# 08_BATT.net
KiCad netlist of a schematic drawn in Altium Designer
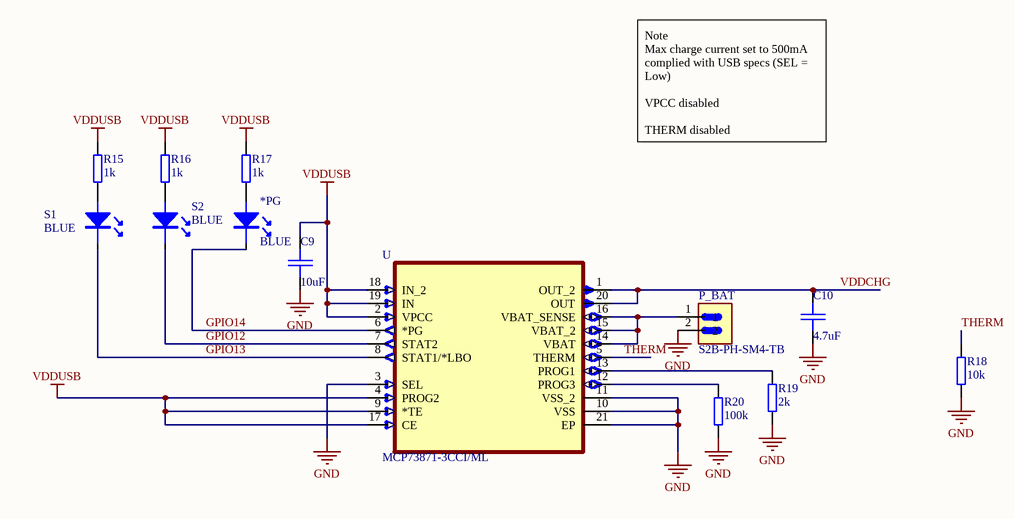
[diagram p0: 08_BATT.SchDoc]

(export (version "E")
  (design (tool "Eeschema 10.0.6"))
  (components
    (comp (ref "*PG")
      (value "BLUE")
      (footprint "SMT_LED_0603")
      (description "SMT LED")
      (libsource (lib "cupmat") (part "SMT_LED_0603"))
    )
    (comp (ref "C9")
      (value "10uF")
      (footprint "SMT_C_0402")
      (description "Surface mount capacitor 0402")
      (libsource (lib "cupmat") (part "SMT_C_0402"))
    )
    (comp (ref "C10")
      (value "4.7uF")
      (footprint "SMT_C_0402")
      (description "Surface mount capacitor 0402")
      (libsource (lib "cupmat") (part "SMT_C_0402"))
    )
    (comp (ref "P_BAT")
      (value "S2B-PH-SM4-TB")
      (footprint "JST_S2B-PH-SM4-TB")
      (description "Connector Header Surface Mount, Right Angle 2 position 0.079 _2.00mm_")
      (fields (field (name "MF") "JST Sales"))
      (libsource (lib "cupmat") (part "S2B-PH-SM4-TB"))
    )
    (comp (ref "R15")
      (value "1k")
      (footprint "SMT_R_0402")
      (description "Surface mount resistor 0402")
      (libsource (lib "cupmat") (part "SMT_R_0402"))
    )
    (comp (ref "R16")
      (value "1k")
      (footprint "SMT_R_0402")
      (description "Surface mount resistor 0402")
      (libsource (lib "cupmat") (part "SMT_R_0402"))
    )
    (comp (ref "R17")
      (value "1k")
      (footprint "SMT_R_0402")
      (description "Surface mount resistor 0402")
      (libsource (lib "cupmat") (part "SMT_R_0402"))
    )
    (comp (ref "R18")
      (value "10k")
      (footprint "SMT_R_0402")
      (description "Surface mount resistor 0402")
      (libsource (lib "cupmat") (part "SMT_R_0402"))
    )
    (comp (ref "R19")
      (value "2k")
      (footprint "SMT_R_0402")
      (description "Surface mount resistor 0402")
      (libsource (lib "cupmat") (part "SMT_R_0402"))
    )
    (comp (ref "R20")
      (value "100k")
      (footprint "SMT_R_0402")
      (description "Surface mount resistor 0402")
      (libsource (lib "cupmat") (part "SMT_R_0402"))
    )
    (comp (ref "S1")
      (value "BLUE")
      (footprint "SMT_LED_0603")
      (description "SMT LED")
      (libsource (lib "cupmat") (part "SMT_LED_0603"))
    )
    (comp (ref "S2")
      (value "BLUE")
      (footprint "SMT_LED_0603")
      (description "SMT LED")
      (libsource (lib "cupmat") (part "SMT_LED_0603"))
    )
    (comp (ref "U")
      (value "MCP73871-3CCI/ML")
      (footprint "MCP73871-3CCI/ML")
      (description "Charger IC Lithium Ion/Polymer 20-QFN _4x4_")
      (fields (field (name "MF") "Microchip"))
      (libsource (lib "cupmat") (part "MCP73871-3CCI/ML"))
    )
  )
  (nets
    (net (code "1") (name "/GPIO12") (class "Default")
      (node (ref "S2") (pin "2") (pinfunction "K_2") (pintype "passive"))
      (node (ref "U") (pin "7") (pinfunction "STAT2_7") (pintype "output"))
    )
    (net (code "2") (name "/GPIO13") (class "Default")
      (node (ref "S1") (pin "2") (pinfunction "K_2") (pintype "passive"))
      (node (ref "U") (pin "8") (pinfunction "STAT1/*LBO_8") (pintype "output"))
    )
    (net (code "3") (name "/GPIO14") (class "Default")
      (node (ref "*PG") (pin "2") (pinfunction "K_2") (pintype "passive"))
      (node (ref "U") (pin "6") (pinfunction "*PG_6") (pintype "output"))
    )
    (net (code "4") (name "/THERM") (class "Default")
      (node (ref "R18") (pin "2") (pinfunction "2_2") (pintype "passive"))
      (node (ref "U") (pin "5") (pinfunction "THERM_5") (pintype "bidirectional"))
    )
    (net (code "5") (name "/VDDCHG") (class "Default")
      (node (ref "C10") (pin "1") (pinfunction "1_1") (pintype "passive"))
      (node (ref "U") (pin "1") (pinfunction "OUT_2_1") (pintype "power_in"))
      (node (ref "U") (pin "20") (pinfunction "OUT_20") (pintype "power_in"))
    )
    (net (code "6") (name "GND") (class "Default")
      (node (ref "C10") (pin "2") (pinfunction "2_2") (pintype "passive"))
      (node (ref "C9") (pin "2") (pinfunction "2_2") (pintype "passive"))
      (node (ref "P_BAT") (pin "2") (pinfunction "2_2") (pintype "passive"))
      (node (ref "R18") (pin "1") (pinfunction "1_1") (pintype "passive"))
      (node (ref "R19") (pin "1") (pinfunction "1_1") (pintype "passive"))
      (node (ref "R20") (pin "1") (pinfunction "1_1") (pintype "passive"))
      (node (ref "U") (pin "10") (pinfunction "VSS_10") (pintype "power_in"))
      (node (ref "U") (pin "11") (pinfunction "VSS_2_11") (pintype "power_in"))
      (node (ref "U") (pin "21") (pinfunction "EP_21") (pintype "passive"))
      (node (ref "U") (pin "3") (pinfunction "SEL_3") (pintype "input"))
    )
    (net (code "7") (name "Net-(*PG-A)") (class "Default")
      (node (ref "*PG") (pin "1") (pinfunction "A_1") (pintype "passive"))
      (node (ref "R17") (pin "1") (pinfunction "1_1") (pintype "passive"))
    )
    (net (code "8") (name "Net-(S1-A)") (class "Default")
      (node (ref "R15") (pin "1") (pinfunction "1_1") (pintype "passive"))
      (node (ref "S1") (pin "1") (pinfunction "A_1") (pintype "passive"))
    )
    (net (code "9") (name "Net-(S2-A)") (class "Default")
      (node (ref "R16") (pin "1") (pinfunction "1_1") (pintype "passive"))
      (node (ref "S2") (pin "1") (pinfunction "A_1") (pintype "passive"))
    )
    (net (code "10") (name "Net-(U-PROG1)") (class "Default")
      (node (ref "R19") (pin "2") (pinfunction "2_2") (pintype "passive"))
      (node (ref "U") (pin "13") (pinfunction "PROG1_13") (pintype "bidirectional"))
    )
    (net (code "11") (name "Net-(U-PROG3)") (class "Default")
      (node (ref "R20") (pin "2") (pinfunction "2_2") (pintype "passive"))
      (node (ref "U") (pin "12") (pinfunction "PROG3_12") (pintype "bidirectional"))
    )
    (net (code "12") (name "Net-(U-VBAT)") (class "Default")
      (node (ref "P_BAT") (pin "1") (pinfunction "1_1") (pintype "passive"))
      (node (ref "U") (pin "14") (pinfunction "VBAT_14") (pintype "bidirectional"))
      (node (ref "U") (pin "15") (pinfunction "VBAT_2_15") (pintype "bidirectional"))
      (node (ref "U") (pin "16") (pinfunction "VBAT_SENSE_16") (pintype "bidirectional"))
    )
    (net (code "13") (name "VDDUSB") (class "Default")
      (node (ref "C9") (pin "1") (pinfunction "1_1") (pintype "passive"))
      (node (ref "R15") (pin "2") (pinfunction "2_2") (pintype "passive"))
      (node (ref "R16") (pin "2") (pinfunction "2_2") (pintype "passive"))
      (node (ref "R17") (pin "2") (pinfunction "2_2") (pintype "passive"))
      (node (ref "U") (pin "17") (pinfunction "CE_17") (pintype "input"))
      (node (ref "U") (pin "18") (pinfunction "IN_2_18") (pintype "input"))
      (node (ref "U") (pin "19") (pinfunction "IN_19") (pintype "input"))
      (node (ref "U") (pin "2") (pinfunction "VPCC_2") (pintype "input"))
      (node (ref "U") (pin "4") (pinfunction "PROG2_4") (pintype "input"))
      (node (ref "U") (pin "9") (pinfunction "*TE_9") (pintype "input"))
    )
  )
)
